# pmod_clock_906.net
KiCad netlist of a schematic drawn in EAGLE
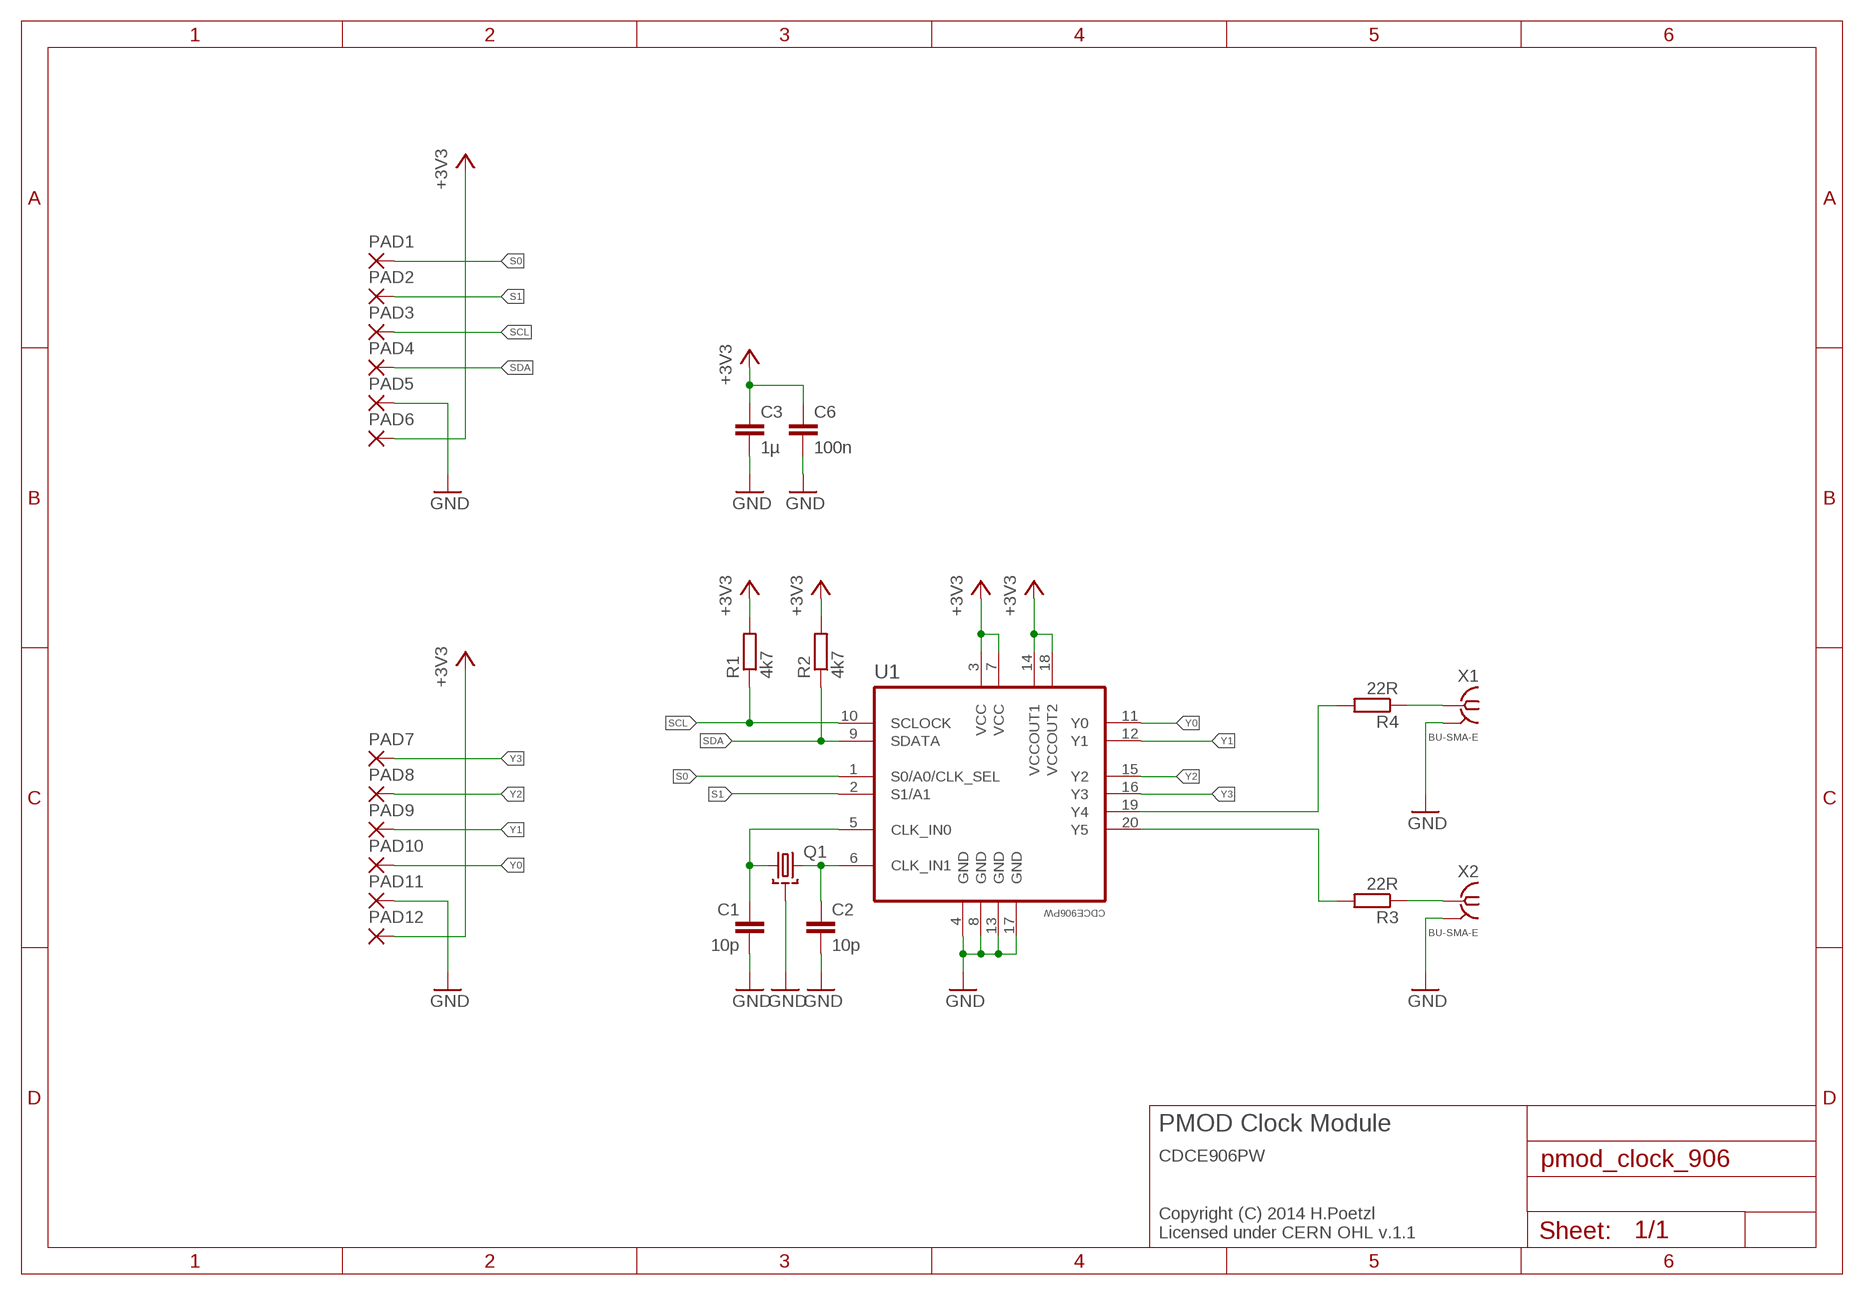
[diagram p0: schematic, sheet 1]

(export (version "E")
  (design (tool "Eeschema 10.0.6"))
  (components
    (comp (ref "C1")
      (value "10p")
      (footprint "eagle-import:C0402K")
      (libsource (lib "eagle-import") (part "C-EUC0402K"))
    )
    (comp (ref "C2")
      (value "10p")
      (footprint "eagle-import:C0402K")
      (libsource (lib "eagle-import") (part "C-EUC0402K"))
    )
    (comp (ref "C3")
      (value "1µ")
      (footprint "eagle-import:C0402")
      (libsource (lib "eagle-import") (part "C-EUC0402"))
    )
    (comp (ref "C6")
      (value "100n")
      (footprint "eagle-import:C0402")
      (libsource (lib "eagle-import") (part "C-EUC0402"))
    )
    (comp (ref "PAD1")
      (value "SMD2HR")
      (footprint "eagle-import:SMD1.27-3.175HR")
      (libsource (lib "eagle-import") (part "SMD2HR"))
    )
    (comp (ref "PAD2")
      (value "SMD2HR")
      (footprint "eagle-import:SMD1.27-3.175HR")
      (libsource (lib "eagle-import") (part "SMD2HR"))
    )
    (comp (ref "PAD3")
      (value "SMD2HR")
      (footprint "eagle-import:SMD1.27-3.175HR")
      (libsource (lib "eagle-import") (part "SMD2HR"))
    )
    (comp (ref "PAD4")
      (value "SMD2HR")
      (footprint "eagle-import:SMD1.27-3.175HR")
      (libsource (lib "eagle-import") (part "SMD2HR"))
    )
    (comp (ref "PAD5")
      (value "SMD2HR")
      (footprint "eagle-import:SMD1.27-3.175HR")
      (libsource (lib "eagle-import") (part "SMD2HR"))
    )
    (comp (ref "PAD6")
      (value "SMD2HR")
      (footprint "eagle-import:SMD1.27-3.175HR")
      (libsource (lib "eagle-import") (part "SMD2HR"))
    )
    (comp (ref "PAD7")
      (value "SMD2HR")
      (footprint "eagle-import:SMD1.27-3.175HR")
      (libsource (lib "eagle-import") (part "SMD2HR"))
    )
    (comp (ref "PAD8")
      (value "SMD2HR")
      (footprint "eagle-import:SMD1.27-3.175HR")
      (libsource (lib "eagle-import") (part "SMD2HR"))
    )
    (comp (ref "PAD9")
      (value "SMD2HR")
      (footprint "eagle-import:SMD1.27-3.175HR")
      (libsource (lib "eagle-import") (part "SMD2HR"))
    )
    (comp (ref "PAD10")
      (value "SMD2HR")
      (footprint "eagle-import:SMD1.27-3.175HR")
      (libsource (lib "eagle-import") (part "SMD2HR"))
    )
    (comp (ref "PAD11")
      (value "SMD2HR")
      (footprint "eagle-import:SMD1.27-3.175HR")
      (libsource (lib "eagle-import") (part "SMD2HR"))
    )
    (comp (ref "PAD12")
      (value "SMD2HR")
      (footprint "eagle-import:SMD1.27-3.175HR")
      (libsource (lib "eagle-import") (part "SMD2HR"))
    )
    (comp (ref "Q1")
      (value "SMD-4P-2G5.0X3.2+3.2X2.5")
      (footprint "eagle-import:MIX")
      (libsource (lib "eagle-import") (part "SMD-4P-2G5.0X3.2+3.2X2.5"))
    )
    (comp (ref "R1")
      (value "4k7")
      (footprint "eagle-import:R0402")
      (libsource (lib "eagle-import") (part "R-EU_R0402"))
    )
    (comp (ref "R2")
      (value "4k7")
      (footprint "eagle-import:R0402")
      (libsource (lib "eagle-import") (part "R-EU_R0402"))
    )
    (comp (ref "R3")
      (value "22R")
      (footprint "eagle-import:R0402")
      (libsource (lib "eagle-import") (part "R-EU_R0402"))
    )
    (comp (ref "R4")
      (value "22R")
      (footprint "eagle-import:R0402")
      (libsource (lib "eagle-import") (part "R-EU_R0402"))
    )
    (comp (ref "U1")
      (value "CDCE906PW")
      (footprint "eagle-import:SOP65P640X120-20N")
      (libsource (lib "eagle-import") (part "CDCE906PW"))
    )
    (comp (ref "X1")
      (value "BU-SMA-E")
      (footprint "eagle-import:SMA-EDGE")
      (libsource (lib "eagle-import") (part "BU-SMA-E"))
    )
    (comp (ref "X2")
      (value "BU-SMA-E")
      (footprint "eagle-import:SMA-EDGE")
      (libsource (lib "eagle-import") (part "BU-SMA-E"))
    )
  )
  (nets
    (net (code "1") (name "+3V3") (class "Default")
      (node (ref "C3") (pin "1") (pinfunction "1_1") (pintype "passive"))
      (node (ref "C6") (pin "1") (pinfunction "1_1") (pintype "passive"))
      (node (ref "PAD12") (pin "1") (pinfunction "P_1") (pintype "passive"))
      (node (ref "PAD6") (pin "1") (pinfunction "P_1") (pintype "passive"))
      (node (ref "R1") (pin "2") (pinfunction "2_2") (pintype "passive"))
      (node (ref "R2") (pin "2") (pinfunction "2_2") (pintype "passive"))
      (node (ref "U1") (pin "14") (pinfunction "VCCOUT1_14") (pintype "output"))
      (node (ref "U1") (pin "18") (pinfunction "VCCOUT2_18") (pintype "output"))
      (node (ref "U1") (pin "3") (pinfunction "VCC_3") (pintype "power_in"))
      (node (ref "U1") (pin "7") (pinfunction "VCC_7") (pintype "power_in"))
    )
    (net (code "2") (name "GND") (class "Default")
      (node (ref "C1") (pin "2") (pinfunction "2_2") (pintype "passive"))
      (node (ref "C2") (pin "2") (pinfunction "2_2") (pintype "passive"))
      (node (ref "C3") (pin "2") (pinfunction "2_2") (pintype "passive"))
      (node (ref "C6") (pin "2") (pinfunction "2_2") (pintype "passive"))
      (node (ref "PAD11") (pin "1") (pinfunction "P_1") (pintype "passive"))
      (node (ref "PAD5") (pin "1") (pinfunction "P_1") (pintype "passive"))
      (node (ref "Q1") (pin "2") (pinfunction "GND_2") (pintype "power_in"))
      (node (ref "Q1") (pin "2@") (pinfunction "GND_2@") (pintype "power_in"))
      (node (ref "Q1") (pin "4") (pinfunction "GND_4") (pintype "power_in"))
      (node (ref "Q1") (pin "4@") (pinfunction "GND_4@") (pintype "power_in"))
      (node (ref "U1") (pin "13") (pinfunction "GND_13") (pintype "passive"))
      (node (ref "U1") (pin "17") (pinfunction "GND_17") (pintype "output"))
      (node (ref "U1") (pin "4") (pinfunction "GND_4") (pintype "passive"))
      (node (ref "U1") (pin "8") (pinfunction "GND_8") (pintype "passive"))
      (node (ref "X1") (pin "2@3") (pinfunction "2_2@3") (pintype "passive"))
      (node (ref "X1") (pin "2@4") (pinfunction "2_2@4") (pintype "passive"))
      (node (ref "X2") (pin "2@3") (pinfunction "2_2@3") (pintype "passive"))
      (node (ref "X2") (pin "2@4") (pinfunction "2_2@4") (pintype "passive"))
    )
    (net (code "3") (name "Net-(R3-Pad1)") (class "Default")
      (node (ref "R3") (pin "1") (pinfunction "1_1") (pintype "passive"))
      (node (ref "X2") (pin "1") (pinfunction "1_1") (pintype "passive"))
    )
    (net (code "4") (name "Net-(R4-Pad1)") (class "Default")
      (node (ref "R4") (pin "1") (pinfunction "1_1") (pintype "passive"))
      (node (ref "X1") (pin "1") (pinfunction "1_1") (pintype "passive"))
    )
    (net (code "5") (name "Net-(U1-CLK_IN0)") (class "Default")
      (node (ref "C1") (pin "1") (pinfunction "1_1") (pintype "passive"))
      (node (ref "Q1") (pin "1") (pinfunction "1_1") (pintype "passive"))
      (node (ref "Q1") (pin "1@") (pinfunction "1_1@") (pintype "passive"))
      (node (ref "U1") (pin "5") (pinfunction "CLK_IN0_5") (pintype "input"))
    )
    (net (code "6") (name "Net-(U1-CLK_IN1)") (class "Default")
      (node (ref "C2") (pin "1") (pinfunction "1_1") (pintype "passive"))
      (node (ref "Q1") (pin "3") (pinfunction "2_3") (pintype "passive"))
      (node (ref "Q1") (pin "3@") (pinfunction "2_3@") (pintype "passive"))
      (node (ref "U1") (pin "6") (pinfunction "CLK_IN1_6") (pintype "input"))
    )
    (net (code "7") (name "Net-(U1-Y4)") (class "Default")
      (node (ref "R4") (pin "2") (pinfunction "2_2") (pintype "passive"))
      (node (ref "U1") (pin "19") (pinfunction "Y4_19") (pintype "output"))
    )
    (net (code "8") (name "Net-(U1-Y5)") (class "Default")
      (node (ref "R3") (pin "2") (pinfunction "2_2") (pintype "passive"))
      (node (ref "U1") (pin "20") (pinfunction "Y5_20") (pintype "output"))
    )
    (net (code "9") (name "S0") (class "Default")
      (node (ref "PAD1") (pin "1") (pinfunction "P_1") (pintype "passive"))
      (node (ref "U1") (pin "1") (pinfunction "S0/A0/CLK_SEL_1") (pintype "input"))
    )
    (net (code "10") (name "S1") (class "Default")
      (node (ref "PAD2") (pin "1") (pinfunction "P_1") (pintype "passive"))
      (node (ref "U1") (pin "2") (pinfunction "S1/A1_2") (pintype "input"))
    )
    (net (code "11") (name "SCL") (class "Default")
      (node (ref "PAD3") (pin "1") (pinfunction "P_1") (pintype "passive"))
      (node (ref "R1") (pin "1") (pinfunction "1_1") (pintype "passive"))
      (node (ref "U1") (pin "10") (pinfunction "SCLOCK_10") (pintype "input"))
    )
    (net (code "12") (name "SDA") (class "Default")
      (node (ref "PAD4") (pin "1") (pinfunction "P_1") (pintype "passive"))
      (node (ref "R2") (pin "1") (pinfunction "1_1") (pintype "passive"))
      (node (ref "U1") (pin "9") (pinfunction "SDATA_9") (pintype "input"))
    )
    (net (code "13") (name "Y0") (class "Default")
      (node (ref "PAD10") (pin "1") (pinfunction "P_1") (pintype "passive"))
      (node (ref "U1") (pin "11") (pinfunction "Y0_11") (pintype "output"))
    )
    (net (code "14") (name "Y1") (class "Default")
      (node (ref "PAD9") (pin "1") (pinfunction "P_1") (pintype "passive"))
      (node (ref "U1") (pin "12") (pinfunction "Y1_12") (pintype "output"))
    )
    (net (code "15") (name "Y2") (class "Default")
      (node (ref "PAD8") (pin "1") (pinfunction "P_1") (pintype "passive"))
      (node (ref "U1") (pin "15") (pinfunction "Y2_15") (pintype "output"))
    )
    (net (code "16") (name "Y3") (class "Default")
      (node (ref "PAD7") (pin "1") (pinfunction "P_1") (pintype "passive"))
      (node (ref "U1") (pin "16") (pinfunction "Y3_16") (pintype "output"))
    )
  )
)
